# USBModule.net
KiCad netlist of a schematic drawn in Altium Designer
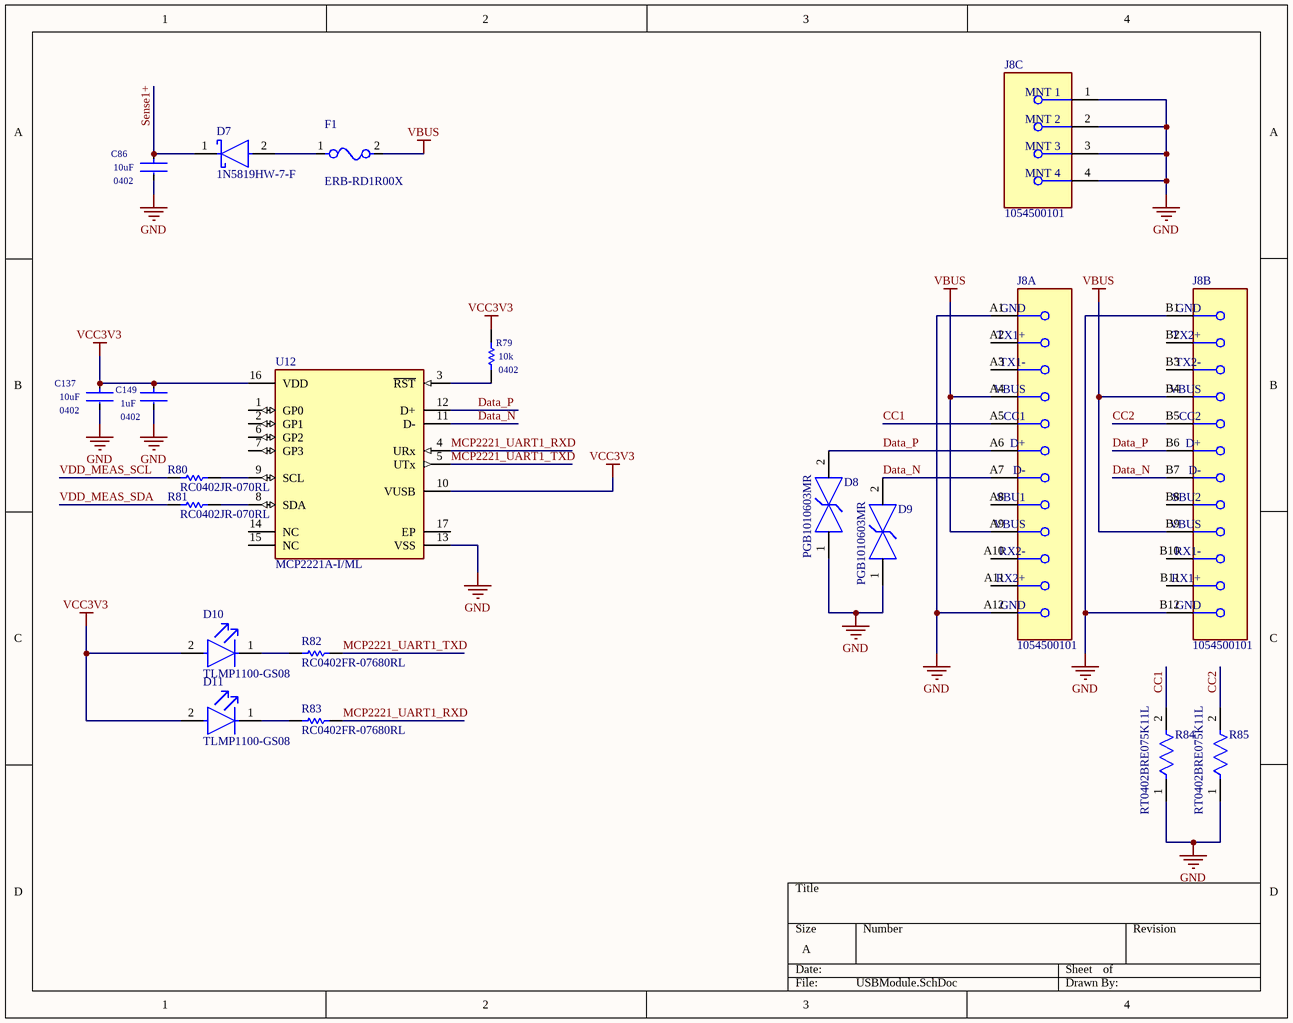
[diagram p0: USBModule.SchDoc]

(export (version "E")
  (design (tool "Eeschema 10.0.6"))
  (components
    (comp (ref "C86")
      (value "GRM155R60J106ME44D")
      (footprint "FP-GRM155-0_2-IPC_B")
      (description "CAP CER 10UF 6.3V X5R 0402")
      (fields
        (field (name "VOLTAGE") "6.3V")
        (field (name "TOLERANCE") "20%")
        (field (name "CASE/PACKAGE") "0402")
        (field (name "CAPACITANCE") "10uF")
      )
      (libsource (lib "Camera_PCB_proj") (part "b4654b650e69147ec39a6b967a45e02"))
    )
    (comp (ref "C137")
      (value "GRM155R60J106ME44D")
      (footprint "FP-GRM155-0_2-IPC_B")
      (description "CAP CER 10UF 6.3V X5R 0402")
      (fields
        (field (name "VOLTAGE") "6.3V")
        (field (name "TOLERANCE") "20%")
        (field (name "CASE/PACKAGE") "0402")
        (field (name "CAPACITANCE") "10uF")
      )
      (libsource (lib "Camera_PCB_proj") (part "b4654b650e69147ec39a6b967a45e02"))
    )
    (comp (ref "C149")
      (value "EMK105BJ105KV-F")
      (footprint "FP-0402-L_1_0_0_05-W_0_5-IPC_A")
      (description "None")
      (fields
        (field (name "TOLERANCE") "10%")
        (field (name "CASE/PACKAGE") "0402")
        (field (name "CAPACITANCE") "1uF")
      )
      (libsource (lib "Camera_PCB_proj") (part "b4654b650e69147ec39a6b967a45e02"))
    )
    (comp (ref "D7")
      (value "1N5819HW-7-F")
      (footprint "FP-SOD123-IPC_A")
      (description "DIODE SCHOTTKY 40V 1A SOD123")
      (libsource (lib "Altium Content Vault") (part "1d6ec82d83fb6aee721767c19dac4b9"))
    )
    (comp (ref "D8")
      (value "PGB1010603MR")
      (footprint "FP-PGB1-0603-CA-MFG")
      (description "TVS DIODE 24V 150V 0603")
      (libsource (lib "Altium Content Vault") (part "876f4347bf90aa6f500f43e3cd03972"))
    )
    (comp (ref "D9")
      (value "PGB1010603MR")
      (footprint "FP-PGB1-0603-CA-MFG")
      (description "TVS DIODE 24V 150V 0603")
      (libsource (lib "Altium Content Vault") (part "876f4347bf90aa6f500f43e3cd03972"))
    )
    (comp (ref "D10")
      (value "TLMP1100-GS08")
      (footprint "FP-6_541-5056_01-4-MFG")
      (description "LED GREEN 0603 SMD")
      (fields
        (field (name "MANUFACTURER") "Vishay")
        (field (name "OCTOPART") "https://octopart.com/tlmp1100-gs08-vishay-55433993")
      )
      (libsource (lib "Altium Content Vault") (part "8706943c75ba83719d021d2fdc84c58"))
    )
    (comp (ref "D11")
      (value "TLMP1100-GS08")
      (footprint "FP-6_541-5056_01-4-MFG")
      (description "LED GREEN 0603 SMD")
      (fields
        (field (name "MANUFACTURER") "Vishay")
        (field (name "OCTOPART") "https://octopart.com/tlmp1100-gs08-vishay-55433993")
      )
      (libsource (lib "Altium Content Vault") (part "8706943c75ba83719d021d2fdc84c58"))
    )
    (comp (ref "F1")
      (value "ERB-RD1R00X")
      (footprint "FP-ERBRD-MFG")
      (description "ERB-RD1R00X Fuse Chip Fast Acting 1A 32V SMD Solder Pad 0402 1 X 0.5 X 0.39mm T/R UL/cUL")
      (libsource (lib "Altium Content Vault") (part "ERB-RD1R00X"))
    )
    (comp (ref "J8")
      (value "1054500101")
      (footprint "FP-1054500101-MFG")
      (description "CONN RCP USB3.1 TYPEC 24P SMD RA")
      (fields
        (field (name "MANUFACTURER") "Molex")
        (field (name "OCTOPART") "https://octopart.com/105450-0101-molex-68082325")
      )
      (libsource (lib "") (part "9808b19ecaf079fb99eed69f0495cd0_1"))
    )
    (comp (ref "R79")
      (value "RC0402FR-0710KL")
      (footprint "RESC1005X40X25NL05T10")
      (fields
        (field (name "MANUFACTURER") "Yageo / Phycomp")
        (field (name "PARAMETER 3") "10k")
        (field (name "PARAMETER 4") "0402")
      )
      (libsource (lib "Camera_PCB_proj") (part "RES"))
    )
    (comp (ref "R80")
      (value "RC0402JR-070RL")
      (footprint "RESC1005X40X25NL05T10")
      (fields (field (name "MANUFACTURER") "Yageo / Phycomp"))
      (libsource (lib "Altium Content Vault") (part "RES"))
    )
    (comp (ref "R81")
      (value "RC0402JR-070RL")
      (footprint "RESC1005X40X25NL05T10")
      (fields (field (name "MANUFACTURER") "Yageo / Phycomp"))
      (libsource (lib "Altium Content Vault") (part "RES"))
    )
    (comp (ref "R82")
      (value "RC0402FR-07680RL")
      (footprint "RESC1005X40X25LL05T10")
      (fields (field (name "MANUFACTURER") "Yageo / Phycomp"))
      (libsource (lib "Altium Content Vault") (part "RES"))
    )
    (comp (ref "R83")
      (value "RC0402FR-07680RL")
      (footprint "RESC1005X40X25LL05T10")
      (fields (field (name "MANUFACTURER") "Yageo / Phycomp"))
      (libsource (lib "Altium Content Vault") (part "RES"))
    )
    (comp (ref "R84")
      (value "RT0402BRE075K11L")
      (footprint "FP-RT0402-MFG")
      (description "RES 5.11K OHM 1/16W .1% SMD 0402")
      (fields
        (field (name "TOLERANCE") "0.001")
        (field (name "OCTOPART") "https://octopart.com/rt0402bre075k11l-yageo-1442753")
      )
      (libsource (lib "Altium Content Vault") (part "1029c3af85768c4190bb7ad29bc67b5"))
    )
    (comp (ref "R85")
      (value "RT0402BRE075K11L")
      (footprint "FP-RT0402-MFG")
      (description "RES 5.11K OHM 1/16W .1% SMD 0402")
      (fields
        (field (name "TOLERANCE") "0.001")
        (field (name "OCTOPART") "https://octopart.com/rt0402bre075k11l-yageo-1442753")
      )
      (libsource (lib "Altium Content Vault") (part "1029c3af85768c4190bb7ad29bc67b5"))
    )
    (comp (ref "U12")
      (value "MCP2221A-I/ML")
      (footprint "FP-C04-127-MFG")
      (description "IC USB TO I2C/UART 16QFN")
      (libsource (lib "Altium Content Vault") (part "9a58687fb20c11cd38d39b7dac8df0f"))
    )
  )
  (nets
    (net (code "1") (name "/CC1") (class "Default")
      (node (ref "J8") (pin "A5") (pinfunction "CC1_A5") (pintype "passive"))
      (node (ref "R84") (pin "2") (pinfunction "2_2") (pintype "passive"))
    )
    (net (code "2") (name "/CC2") (class "Default")
      (node (ref "J8") (pin "B5") (pinfunction "CC2_B5") (pintype "passive"))
      (node (ref "R85") (pin "2") (pinfunction "2_2") (pintype "passive"))
    )
    (net (code "3") (name "/Data_N") (class "Default")
      (node (ref "D9") (pin "2") (pinfunction "2_2") (pintype "passive"))
      (node (ref "J8") (pin "A7") (pinfunction "D-_A7") (pintype "passive"))
      (node (ref "J8") (pin "B7") (pinfunction "D-_B7") (pintype "passive"))
      (node (ref "U12") (pin "11") (pinfunction "D-_11") (pintype "passive"))
    )
    (net (code "4") (name "/Data_P") (class "Default")
      (node (ref "D8") (pin "2") (pinfunction "2_2") (pintype "passive"))
      (node (ref "J8") (pin "A6") (pinfunction "D+_A6") (pintype "passive"))
      (node (ref "J8") (pin "B6") (pinfunction "D+_B6") (pintype "passive"))
      (node (ref "U12") (pin "12") (pinfunction "D+_12") (pintype "passive"))
    )
    (net (code "5") (name "/MCP2221_UART1_RXD") (class "Default")
      (node (ref "R83") (pin "2") (pinfunction "2_2") (pintype "passive"))
      (node (ref "U12") (pin "4") (pinfunction "URx_4") (pintype "input"))
    )
    (net (code "6") (name "/MCP2221_UART1_TXD") (class "Default")
      (node (ref "R82") (pin "2") (pinfunction "2_2") (pintype "passive"))
      (node (ref "U12") (pin "5") (pinfunction "UTx_5") (pintype "output"))
    )
    (net (code "7") (name "/Sense1+") (class "Default")
      (node (ref "C86") (pin "1") (pinfunction "1_1") (pintype "passive"))
      (node (ref "D7") (pin "1") (pinfunction "C_1") (pintype "passive"))
    )
    (net (code "8") (name "/VDD_MEAS_SCL") (class "Default")
      (node (ref "R80") (pin "1") (pinfunction "1_1") (pintype "passive"))
    )
    (net (code "9") (name "/VDD_MEAS_SDA") (class "Default")
      (node (ref "R81") (pin "1") (pinfunction "1_1") (pintype "passive"))
    )
    (net (code "10") (name "GND") (class "Default")
      (node (ref "C137") (pin "2") (pinfunction "2_2") (pintype "passive"))
      (node (ref "C149") (pin "2") (pinfunction "2_2") (pintype "passive"))
      (node (ref "C86") (pin "2") (pinfunction "2_2") (pintype "passive"))
      (node (ref "D8") (pin "1") (pinfunction "1_1") (pintype "passive"))
      (node (ref "D9") (pin "1") (pinfunction "1_1") (pintype "passive"))
      (node (ref "J8") (pin "1") (pinfunction "MNT_1_1") (pintype "passive"))
      (node (ref "J8") (pin "2") (pinfunction "MNT_2_2") (pintype "passive"))
      (node (ref "J8") (pin "3") (pinfunction "MNT_3_3") (pintype "passive"))
      (node (ref "J8") (pin "4") (pinfunction "MNT_4_4") (pintype "passive"))
      (node (ref "J8") (pin "A1") (pinfunction "GND_A1") (pintype "passive"))
      (node (ref "J8") (pin "A12") (pinfunction "GND_A12") (pintype "passive"))
      (node (ref "J8") (pin "B1") (pinfunction "GND_B1") (pintype "passive"))
      (node (ref "J8") (pin "B12") (pinfunction "GND_B12") (pintype "passive"))
      (node (ref "R84") (pin "1") (pinfunction "1_1") (pintype "passive"))
      (node (ref "R85") (pin "1") (pinfunction "1_1") (pintype "passive"))
      (node (ref "U12") (pin "13") (pinfunction "VSS_13") (pintype "power_in"))
    )
    (net (code "11") (name "Net-(D7-A)") (class "Default")
      (node (ref "D7") (pin "2") (pinfunction "A_2") (pintype "passive"))
      (node (ref "F1") (pin "1") (pinfunction "1_1") (pintype "passive"))
    )
    (net (code "12") (name "Net-(D10-C)") (class "Default")
      (node (ref "D10") (pin "1") (pinfunction "C_1") (pintype "passive"))
      (node (ref "R82") (pin "1") (pinfunction "1_1") (pintype "passive"))
    )
    (net (code "13") (name "Net-(D11-C)") (class "Default")
      (node (ref "D11") (pin "1") (pinfunction "C_1") (pintype "passive"))
      (node (ref "R83") (pin "1") (pinfunction "1_1") (pintype "passive"))
    )
    (net (code "14") (name "Net-(U12-SCL)") (class "Default")
      (node (ref "R80") (pin "2") (pinfunction "2_2") (pintype "passive"))
      (node (ref "U12") (pin "9") (pinfunction "SCL_9") (pintype "bidirectional"))
    )
    (net (code "15") (name "Net-(U12-SDA)") (class "Default")
      (node (ref "R81") (pin "2") (pinfunction "2_2") (pintype "passive"))
      (node (ref "U12") (pin "8") (pinfunction "SDA_8") (pintype "bidirectional"))
    )
    (net (code "16") (name "Net-(U12-~{RST})") (class "Default")
      (node (ref "R79") (pin "1") (pinfunction "1_1") (pintype "passive"))
      (node (ref "U12") (pin "3") (pinfunction "~{RST}_3") (pintype "input"))
    )
    (net (code "17") (name "VBUS") (class "Default")
      (node (ref "F1") (pin "2") (pinfunction "2_2") (pintype "passive"))
      (node (ref "J8") (pin "A4") (pinfunction "VBUS_A4") (pintype "passive"))
      (node (ref "J8") (pin "A9") (pinfunction "VBUS_A9") (pintype "passive"))
      (node (ref "J8") (pin "B4") (pinfunction "VBUS_B4") (pintype "passive"))
      (node (ref "J8") (pin "B9") (pinfunction "VBUS_B9") (pintype "passive"))
    )
    (net (code "18") (name "VCC3V3") (class "Default")
      (node (ref "C137") (pin "1") (pinfunction "1_1") (pintype "passive"))
      (node (ref "C149") (pin "1") (pinfunction "1_1") (pintype "passive"))
      (node (ref "D10") (pin "2") (pinfunction "A_2") (pintype "passive"))
      (node (ref "D11") (pin "2") (pinfunction "A_2") (pintype "passive"))
      (node (ref "R79") (pin "2") (pinfunction "2_2") (pintype "passive"))
      (node (ref "U12") (pin "10") (pinfunction "VUSB_10") (pintype "power_in"))
      (node (ref "U12") (pin "16") (pinfunction "VDD_16") (pintype "power_in"))
    )
    (net (code "19") (name "unconnected-(J8A-RX2+-PadA11)") (class "Default")
      (node (ref "J8") (pin "A11") (pinfunction "RX2+_A11") (pintype "passive"))
    )
    (net (code "20") (name "unconnected-(J8A-RX2--PadA10)") (class "Default")
      (node (ref "J8") (pin "A10") (pinfunction "RX2-_A10") (pintype "passive"))
    )
    (net (code "21") (name "unconnected-(J8A-SBU1-PadA8)") (class "Default")
      (node (ref "J8") (pin "A8") (pinfunction "SBU1_A8") (pintype "passive"))
    )
    (net (code "22") (name "unconnected-(J8A-TX1+-PadA2)") (class "Default")
      (node (ref "J8") (pin "A2") (pinfunction "TX1+_A2") (pintype "passive"))
    )
    (net (code "23") (name "unconnected-(J8A-TX1--PadA3)") (class "Default")
      (node (ref "J8") (pin "A3") (pinfunction "TX1-_A3") (pintype "passive"))
    )
    (net (code "24") (name "unconnected-(J8B-RX1+-PadB11)") (class "Default")
      (node (ref "J8") (pin "B11") (pinfunction "RX1+_B11") (pintype "passive"))
    )
    (net (code "25") (name "unconnected-(J8B-RX1--PadB10)") (class "Default")
      (node (ref "J8") (pin "B10") (pinfunction "RX1-_B10") (pintype "passive"))
    )
    (net (code "26") (name "unconnected-(J8B-SBU2-PadB8)") (class "Default")
      (node (ref "J8") (pin "B8") (pinfunction "SBU2_B8") (pintype "passive"))
    )
    (net (code "27") (name "unconnected-(J8B-TX2+-PadB2)") (class "Default")
      (node (ref "J8") (pin "B2") (pinfunction "TX2+_B2") (pintype "passive"))
    )
    (net (code "28") (name "unconnected-(J8B-TX2--PadB3)") (class "Default")
      (node (ref "J8") (pin "B3") (pinfunction "TX2-_B3") (pintype "passive"))
    )
    (net (code "29") (name "unconnected-(U12-EP-Pad17)") (class "Default")
      (node (ref "U12") (pin "17") (pinfunction "EP_17") (pintype "power_in"))
    )
    (net (code "30") (name "unconnected-(U12-GP0-Pad1)") (class "Default")
      (node (ref "U12") (pin "1") (pinfunction "GP0_1") (pintype "bidirectional"))
    )
    (net (code "31") (name "unconnected-(U12-GP1-Pad2)") (class "Default")
      (node (ref "U12") (pin "2") (pinfunction "GP1_2") (pintype "bidirectional"))
    )
    (net (code "32") (name "unconnected-(U12-GP2-Pad6)") (class "Default")
      (node (ref "U12") (pin "6") (pinfunction "GP2_6") (pintype "bidirectional"))
    )
    (net (code "33") (name "unconnected-(U12-GP3-Pad7)") (class "Default")
      (node (ref "U12") (pin "7") (pinfunction "GP3_7") (pintype "bidirectional"))
    )
    (net (code "34") (name "unconnected-(U12-NC-Pad14)") (class "Default")
      (node (ref "U12") (pin "14") (pinfunction "NC_14") (pintype "passive"))
    )
    (net (code "35") (name "unconnected-(U12-NC-Pad15)") (class "Default")
      (node (ref "U12") (pin "15") (pinfunction "NC_15") (pintype "passive"))
    )
  )
)
